# SoftCore_SA_P2_PG6.net
KiCad netlist of a schematic drawn in Altium Designer
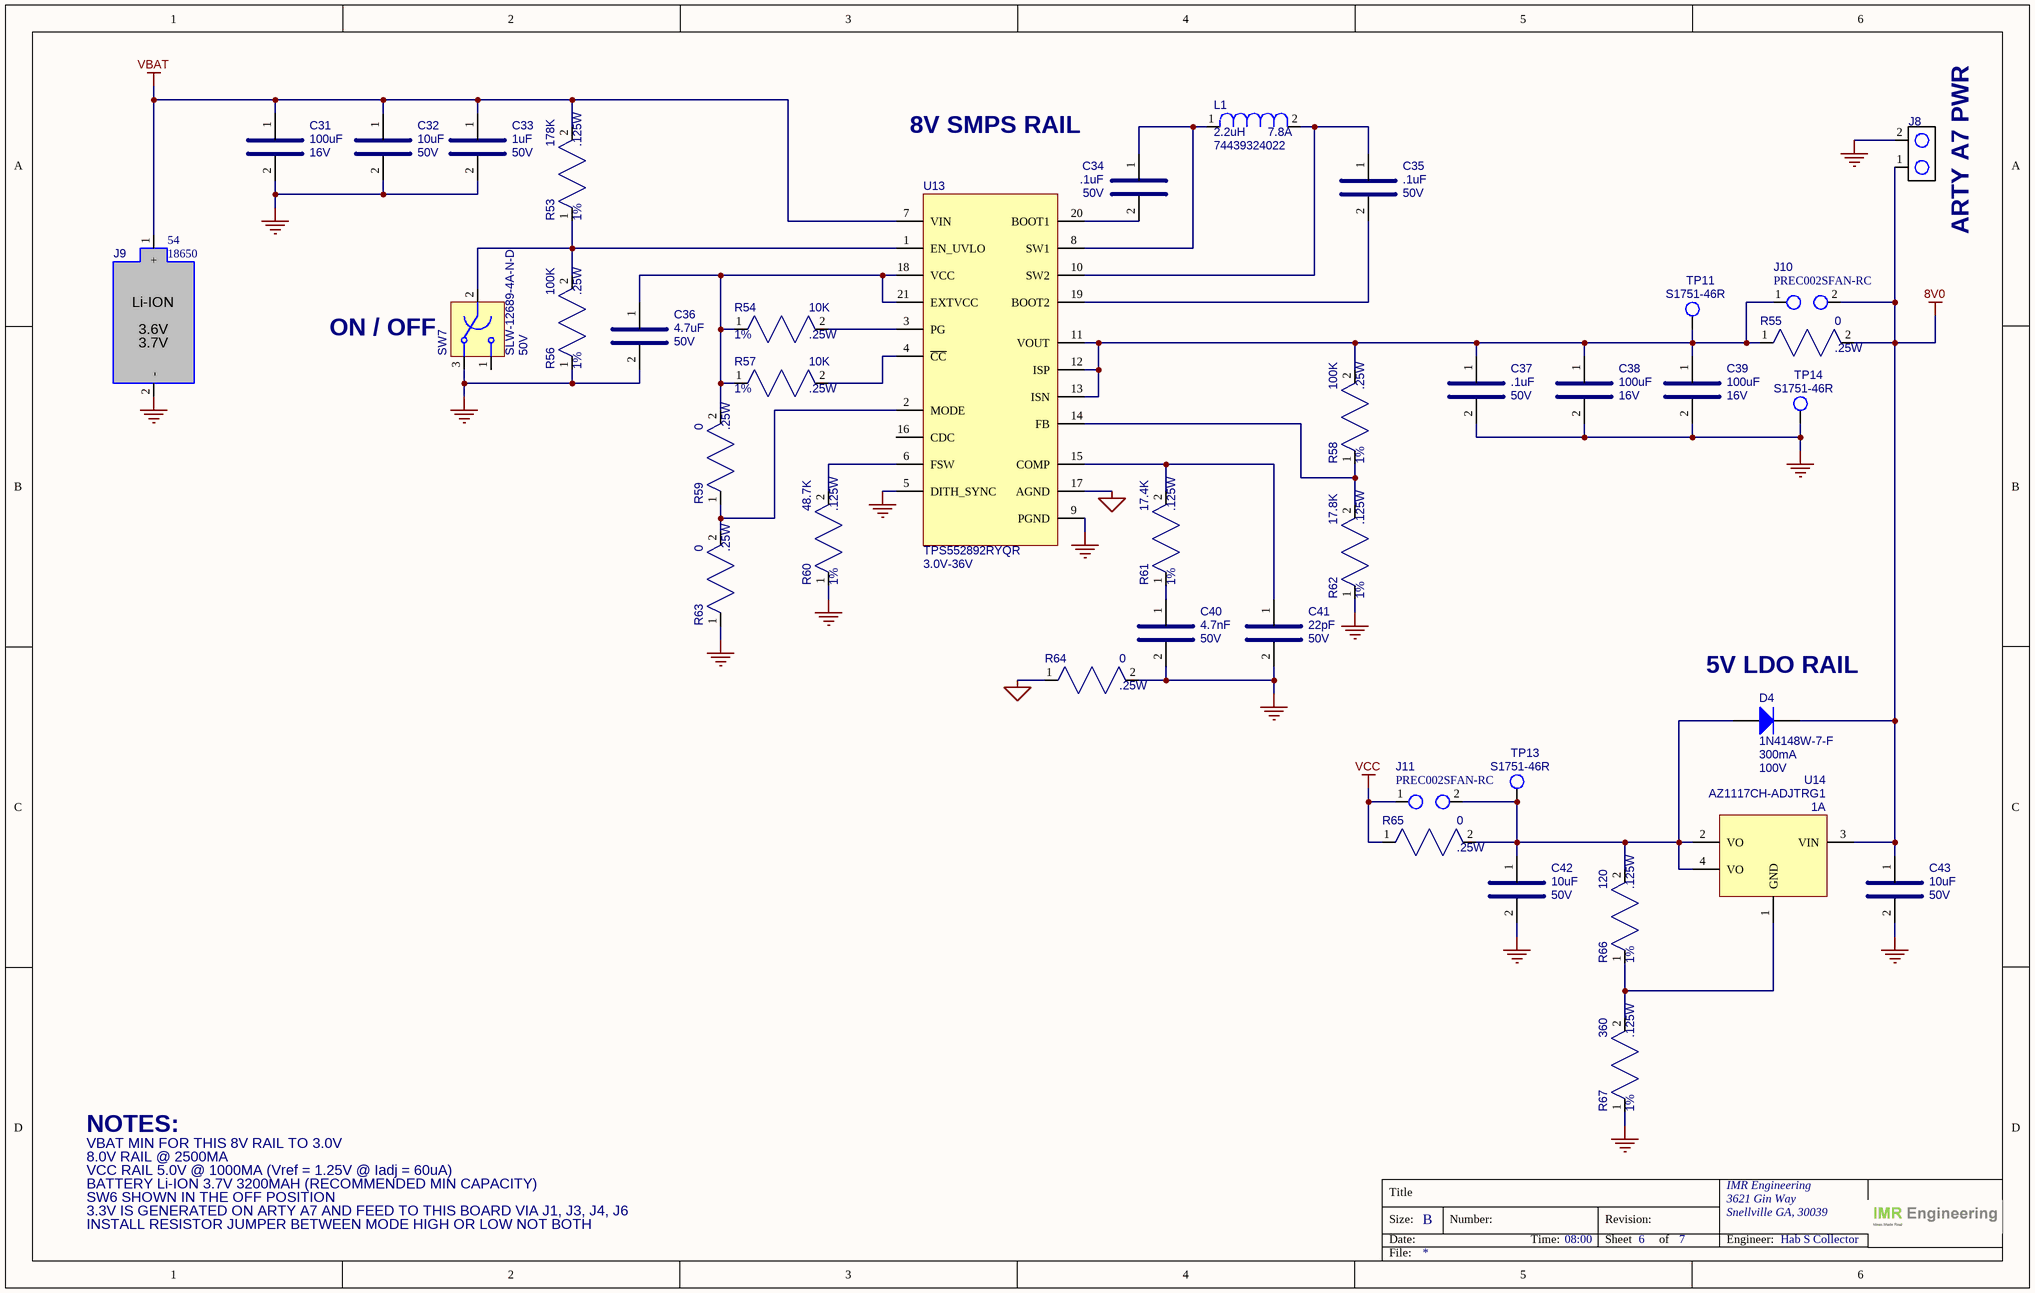
[diagram p0: SoftCore_SA_P2_PG6.SchDoc]

(export (version "E")
  (design (tool "Eeschema 10.0.6"))
  (components
    (comp (ref "C31")
      (value "100uF")
      (footprint "CAP_1210")
      (description "CAP CER 100UF 16V X7S SMD")
      (fields
        (field (name "MFG") "Taiyo Yuden")
        (field (name "VOLTAGE") "16V")
        (field (name "Comment") "EMK325ABJ107MM-P")
      )
      (libsource (lib "IMR_LIB_SCH_R2") (part "CAP_SMD_100UF_16V_SMD"))
    )
    (comp (ref "C32")
      (value "10uF")
      (footprint "CAP_0805")
      (description "CAP CER 10UF 50V X5R 0805")
      (fields
        (field (name "MFG") "Murata Electronics")
        (field (name "VOLTAGE") "50V")
        (field (name "Comment") "GRM21BR61H106KE43L")
      )
      (libsource (lib "IMR_LIB_SCH_R2") (part "CAP_SMD_10UF_50V_0805"))
    )
    (comp (ref "C33")
      (value "1uF")
      (footprint "CAP_0805")
      (description "CAP CER 1UF 50V X7R 0805")
      (fields
        (field (name "MFG") "KYOCERA AVX")
        (field (name "VOLTAGE") "50V")
        (field (name "Comment") "08055C105K4T2A")
      )
      (libsource (lib "IMR_LIB_SCH_R2") (part "CAP_SMD_1UF_50V_0805"))
    )
    (comp (ref "C34")
      (value ".1uF")
      (footprint "CAP_0805")
      (description "CAP CER 0.1UF 50V X7R 0805")
      (fields
        (field (name "MFG") "KYOCERA AVX")
        (field (name "VOLTAGE") "50V")
        (field (name "Comment") "KGM21NR71H104KT")
      )
      (libsource (lib "IMR_LIB_SCH_R2") (part "CAP_SMD_0.1UF_50V_0805"))
    )
    (comp (ref "C35")
      (value ".1uF")
      (footprint "CAP_0805")
      (description "CAP CER 0.1UF 50V X7R 0805")
      (fields
        (field (name "MFG") "KYOCERA AVX")
        (field (name "VOLTAGE") "50V")
        (field (name "Comment") "KGM21NR71H104KT")
      )
      (libsource (lib "IMR_LIB_SCH_R2") (part "CAP_SMD_0.1UF_50V_0805"))
    )
    (comp (ref "C36")
      (value "4.7uF")
      (footprint "CAP_0805")
      (description "CAP CER 4.7UF 50V X5R 0805")
      (fields
        (field (name "MFG") "Murata Electronics")
        (field (name "VOLTAGE") "50V")
        (field (name "Comment") "GRM21BR61H475KE51L")
      )
      (libsource (lib "IMR_LIB_SCH_R2") (part "CAP_SMD_4.7UF_50V_0805"))
    )
    (comp (ref "C37")
      (value ".1uF")
      (footprint "CAP_0805")
      (description "CAP CER 0.1UF 50V X7R 0805")
      (fields
        (field (name "MFG") "KYOCERA AVX")
        (field (name "VOLTAGE") "50V")
        (field (name "Comment") "KGM21NR71H104KT")
      )
      (libsource (lib "IMR_LIB_SCH_R2") (part "CAP_SMD_0.1UF_50V_0805"))
    )
    (comp (ref "C38")
      (value "100uF")
      (footprint "CAP_1210")
      (description "CAP CER 100UF 16V X7S SMD")
      (fields
        (field (name "MFG") "Taiyo Yuden")
        (field (name "VOLTAGE") "16V")
        (field (name "Comment") "EMK325ABJ107MM-P")
      )
      (libsource (lib "IMR_LIB_SCH_R2") (part "CAP_SMD_100UF_16V_SMD"))
    )
    (comp (ref "C39")
      (value "100uF")
      (footprint "CAP_1210")
      (description "CAP CER 100UF 16V X7S SMD")
      (fields
        (field (name "MFG") "Taiyo Yuden")
        (field (name "VOLTAGE") "16V")
        (field (name "Comment") "EMK325ABJ107MM-P")
      )
      (libsource (lib "IMR_LIB_SCH_R2") (part "CAP_SMD_100UF_16V_SMD"))
    )
    (comp (ref "C40")
      (value "4.7nF")
      (footprint "CAP_0805")
      (description "CAP CER 4.7NF 50V X7R 0805")
      (fields
        (field (name "MFG") "KEMET")
        (field (name "VOLTAGE") "50V")
        (field (name "Comment") "C0805C472K5RACAUTO")
      )
      (libsource (lib "IMR_LIB_SCH_R2") (part "CAP_SMD_4.7NF_50V_0805"))
    )
    (comp (ref "C41")
      (value "22pF")
      (footprint "CAP_0805")
      (description "CAP CER 22PF 50V X7R 0805")
      (fields
        (field (name "MFG") "KEMET")
        (field (name "VOLTAGE") "50V")
        (field (name "Comment") "C0805C220K5RACAUTO")
      )
      (libsource (lib "IMR_LIB_SCH_R2") (part "CAP_SMD_22PF_50V_0805"))
    )
    (comp (ref "C42")
      (value "10uF")
      (footprint "CAP_0805")
      (description "CAP CER 10UF 50V X5R 0805")
      (fields
        (field (name "MFG") "Murata Electronics")
        (field (name "VOLTAGE") "50V")
        (field (name "Comment") "GRM21BR61H106KE43L")
      )
      (libsource (lib "IMR_LIB_SCH_R2") (part "CAP_SMD_10UF_50V_0805"))
    )
    (comp (ref "C43")
      (value "10uF")
      (footprint "CAP_0805")
      (description "CAP CER 10UF 50V X5R 0805")
      (fields
        (field (name "MFG") "Murata Electronics")
        (field (name "VOLTAGE") "50V")
        (field (name "Comment") "GRM21BR61H106KE43L")
      )
      (libsource (lib "IMR_LIB_SCH_R2") (part "CAP_SMD_10UF_50V_0805"))
    )
    (comp (ref "D4")
      (value "100V")
      (footprint "SOD123")
      (description "RELAY REED SPDT 250MA 5V")
      (fields
        (field (name "MFG") "Diodes Inc")
        (field (name "MFG_PN") "1N4148W-7-F")
        (field (name "CURRENT") "300mA")
        (field (name "Comment") "1N4148W-7-F")
      )
      (libsource (lib "IMR_LIB_SCH_R2") (part "DIODE_1N4148W-7-F"))
    )
    (comp (ref "J8")
      (value "PREC002SFAN-RC")
      (footprint "HDR_1X2_100MILL")
      (description "CONN HEADER VERT 2POS 2.54MM")
      (fields (field (name "MFG") "Sullins Connector Solutions"))
      (libsource (lib "IMR_LIB_SCH_R2") (part "CONN_HEADER_2P_100MIL_VERT"))
    )
    (comp (ref "J9")
      (value "18650")
      (footprint "CONN_BATTERY_18650")
      (description "CONN HEADER VERT 2POS 2.54MM")
      (fields
        (field (name "MFG") "Keystone Electronics")
        (field (name "MFG_PN") "54")
        (field (name "Comment") "54")
      )
      (libsource (lib "IMR_LIB_SCH_R2") (part "CONN_BATT_18650"))
    )
    (comp (ref "J10")
      (value "PREC002SFAN-RC")
      (footprint "HDR_1X2_100MILL")
      (description "CONN HEADER VERT 2POS 2.54MM")
      (fields (field (name "MFG") "Sullins Connector Solutions"))
      (libsource (lib "IMR_LIB_SCH_R2") (part "CONN_JUMPER_2P_100MIL_VERT"))
    )
    (comp (ref "J11")
      (value "PREC002SFAN-RC")
      (footprint "HDR_1X2_100MILL")
      (description "CONN HEADER VERT 2POS 2.54MM")
      (fields (field (name "MFG") "Sullins Connector Solutions"))
      (libsource (lib "IMR_LIB_SCH_R2") (part "CONN_JUMPER_2P_100MIL_VERT"))
    )
    (comp (ref "L1")
      (value "2.2uH")
      (footprint "WE-XHMI_4030")
      (description "POWER INDUCTOR 4030; 2.2UH; 7.80")
      (fields
        (field (name "MFG") "Würth Elektronik")
        (field (name "TOLERANCE") "20%")
        (field (name "MFG_PN") "74439324022")
        (field (name "CURRENT") "7.8A")
      )
      (libsource (lib "IMR_LIB_SCH_R2") (part "INDUCTOR_74439324022"))
    )
    (comp (ref "R53")
      (value "178K")
      (footprint "RES_0805")
      (description "RES SMD 178K OHM 1% 1/8W 0805")
      (fields
        (field (name "MFG") "Yageo")
        (field (name "POWER") ".125W")
        (field (name "TOLERANCE") "1%")
        (field (name "Comment") "RC0805FR-07178KL")
      )
      (libsource (lib "IMR_LIB_SCH_R2") (part "RES_SMD_178K_0805_1/8W_1%"))
    )
    (comp (ref "R54")
      (value "10K")
      (footprint "RES_0805")
      (description "RES SMD 10K OHM 1% 1/4W 0805")
      (fields
        (field (name "MFG") "Yageo")
        (field (name "POWER") ".25W")
        (field (name "TOLERANCE") "1%")
        (field (name "Comment") "RC0805FR-7W10KL")
      )
      (libsource (lib "IMR_LIB_SCH_R2") (part "RES_SMD_10K_0805_1/4W_1%"))
    )
    (comp (ref "R55")
      (value "0")
      (footprint "RES_0805")
      (description "RES SMD 0 OHM 1% 1/8W 0805")
      (fields (field (name "MFG") "Yageo") (field (name "TOLERANCE") "1%") (field (name "POWER") ".25W"))
      (libsource (lib "IMR_LIB_SCH_R2") (part "RES_SMD_0_0805_1/8W_1%"))
    )
    (comp (ref "R56")
      (value "100K")
      (footprint "RES_0805")
      (description "RES SMD 100K OHM 1% 1/4W 0805")
      (fields
        (field (name "MFG") "Yageo")
        (field (name "POWER") ".25W")
        (field (name "TOLERANCE") "1%")
        (field (name "Comment") "RC0805FR-07100KL")
      )
      (libsource (lib "IMR_LIB_SCH_R2") (part "RES_SMD_100K_0805_1/4W_1%"))
    )
    (comp (ref "R57")
      (value "10K")
      (footprint "RES_0805")
      (description "RES SMD 10K OHM 1% 1/4W 0805")
      (fields
        (field (name "MFG") "Yageo")
        (field (name "POWER") ".25W")
        (field (name "TOLERANCE") "1%")
        (field (name "Comment") "RC0805FR-7W10KL")
      )
      (libsource (lib "IMR_LIB_SCH_R2") (part "RES_SMD_10K_0805_1/4W_1%"))
    )
    (comp (ref "R58")
      (value "100K")
      (footprint "RES_0805")
      (description "RES SMD 100K OHM 1% 1/4W 0805")
      (fields
        (field (name "MFG") "Yageo")
        (field (name "POWER") ".25W")
        (field (name "TOLERANCE") "1%")
        (field (name "Comment") "RC0805FR-07100KL")
      )
      (libsource (lib "IMR_LIB_SCH_R2") (part "RES_SMD_100K_0805_1/4W_1%"))
    )
    (comp (ref "R59")
      (value "0")
      (footprint "RES_0805")
      (description "RES SMD 0 OHM 1% 1/8W 0805")
      (fields (field (name "MFG") "Yageo") (field (name "TOLERANCE") "1%") (field (name "POWER") ".25W"))
      (libsource (lib "IMR_LIB_SCH_R2") (part "RES_SMD_0_0805_1/8W_1%"))
    )
    (comp (ref "R60")
      (value "48.7K")
      (footprint "RES_0805")
      (description "RES SMD 48.7K OHM 1% 1/8W 0805")
      (fields
        (field (name "MFG") "Yageo")
        (field (name "POWER") ".125W")
        (field (name "TOLERANCE") "1%")
        (field (name "Comment") "RC0805FR-0748K7L")
      )
      (libsource (lib "IMR_LIB_SCH_R2") (part "RES_SMD_48.7K_0805_1/8W_1%"))
    )
    (comp (ref "R61")
      (value "17.4K")
      (footprint "RES_0805")
      (description "RES SMD 17.4K OHM 1% 1/8W 0805")
      (fields
        (field (name "MFG") "Yageo")
        (field (name "POWER") ".125W")
        (field (name "TOLERANCE") "1%")
        (field (name "Comment") "RC0805FR-0717K4L")
      )
      (libsource (lib "IMR_LIB_SCH_R2") (part "RES_SMD_17.4K_0805_1/8W_1%"))
    )
    (comp (ref "R62")
      (value "17.8K")
      (footprint "RES_0805")
      (description "RES SMD 17.8K OHM 1% 1/8W 0805")
      (fields
        (field (name "MFG") "Yageo")
        (field (name "POWER") ".125W")
        (field (name "TOLERANCE") "1%")
        (field (name "Comment") "RC0805FR-0717K8L")
      )
      (libsource (lib "IMR_LIB_SCH_R2") (part "RES_SMD_17.8K_0805_1/8W_1%"))
    )
    (comp (ref "R63")
      (value "0")
      (footprint "RES_0805")
      (description "RES SMD 0 OHM 1% 1/8W 0805")
      (fields (field (name "MFG") "Yageo") (field (name "TOLERANCE") "1%") (field (name "POWER") ".25W"))
      (libsource (lib "IMR_LIB_SCH_R2") (part "RES_SMD_0_0805_1/8W_1%"))
    )
    (comp (ref "R64")
      (value "0")
      (footprint "RES_0805")
      (description "RES SMD 0 OHM 1% 1/8W 0805")
      (fields (field (name "MFG") "Yageo") (field (name "TOLERANCE") "1%") (field (name "POWER") ".25W"))
      (libsource (lib "IMR_LIB_SCH_R2") (part "RES_SMD_0_0805_1/8W_1%"))
    )
    (comp (ref "R65")
      (value "0")
      (footprint "RES_0805")
      (description "RES SMD 0 OHM 1% 1/8W 0805")
      (fields (field (name "MFG") "Yageo") (field (name "TOLERANCE") "1%") (field (name "POWER") ".25W"))
      (libsource (lib "IMR_LIB_SCH_R2") (part "RES_SMD_0_0805_1/8W_1%"))
    )
    (comp (ref "R66")
      (value "120")
      (footprint "RES_0805")
      (description "RES SMD 2.49K OHM 1% 1/8W 0805")
      (fields
        (field (name "MFG") "Yageo")
        (field (name "POWER") ".125W")
        (field (name "TOLERANCE") "1%")
        (field (name "Comment") "RC0805FR-132K49L")
      )
      (libsource (lib "IMR_LIB_SCH_R2") (part "RES_SMD_2.49K_0805_1/8W_1%"))
    )
    (comp (ref "R67")
      (value "360")
      (footprint "RES_0805")
      (description "RES SMD 6.81K OHM 1% 1/8W 0805")
      (fields
        (field (name "MFG") "Yageo")
        (field (name "POWER") ".125W")
        (field (name "TOLERANCE") "1%")
        (field (name "Comment") "RC0805FR-076K81L")
      )
      (libsource (lib "IMR_LIB_SCH_R2") (part "RES_SMD_6.81K_0805_1/8W_1%"))
    )
    (comp (ref "SW7")
      (value "50V")
      (footprint "SLW126894AND")
      (description "SWITCH SLIDE SPDT 300MA 50V")
      (fields
        (field (name "MFG") "Same Sky")
        (field (name "MFG_PN") "SLW-12689-4A-N-D")
        (field (name "Comment") "SLW-12689-4A-N-D")
      )
      (libsource (lib "IMR_LIB_SCH_R2") (part "SWITCH_SLW-12689-4A-N-D"))
    )
    (comp (ref "TP11")
      (value "S1751-46R")
      (footprint "HARWIN_S1751")
      (description "PCB TEST POINT CONNECT")
      (fields (field (name "MFG") "Harwin Inc") (field (name "MFG_PN") "S1751-46R"))
      (libsource (lib "IMR_LIB_SCH_R2") (part "CONN_TEST_POINT_S1751-46R"))
    )
    (comp (ref "TP13")
      (value "S1751-46R")
      (footprint "HARWIN_S1751")
      (description "PCB TEST POINT CONNECT")
      (fields (field (name "MFG") "Harwin Inc") (field (name "MFG_PN") "S1751-46R"))
      (libsource (lib "IMR_LIB_SCH_R2") (part "CONN_TEST_POINT_S1751-46R"))
    )
    (comp (ref "TP14")
      (value "S1751-46R")
      (footprint "HARWIN_S1751")
      (description "PCB TEST POINT CONNECT")
      (fields (field (name "MFG") "Harwin Inc") (field (name "MFG_PN") "S1751-46R"))
      (libsource (lib "IMR_LIB_SCH_R2") (part "CONN_TEST_POINT_S1751-46R"))
    )
    (comp (ref "U13")
      (value "3.0V-36V")
      (footprint "CONV_TPS552892RYQR")
      (description "IC REG BUCK ADJ 1A 16HTSSOP")
      (fields
        (field (name "MFG") "Texas Instruments")
        (field (name "MFG_PN") "TPS552892RYQR")
        (field (name "Comment") "TPS552892RYQR")
      )
      (libsource (lib "IMR_LIB_SCH_R2") (part "IC_SMPS_TPS552892RYQR"))
    )
    (comp (ref "U14")
      (value "AZ1117CH-ADJTRG1")
      (footprint "SOT223")
      (description "IC REG BUCK ADJ 2A SOT23")
      (fields
        (field (name "MFG") "Diodes Incorporated")
        (field (name "CURRENT") "1A")
        (field (name "MFG_PN") "AZ1117CH-ADJTRG1")
      )
      (libsource (lib "IMR_LIB_SCH_R2") (part "IC_REG_AZ1117CH-ADJTRG1"))
    )
  )
  (nets
    (net (code "1") (name "8V0") (class "Default")
      (node (ref "C43") (pin "1") (pinfunction "1_1") (pintype "passive"))
      (node (ref "D4") (pin "2") (pinfunction "K_2") (pintype "passive"))
      (node (ref "J10") (pin "2") (pintype "passive"))
      (node (ref "J8") (pin "1") (pintype "passive"))
      (node (ref "R55") (pin "2") (pinfunction "2_2") (pintype "passive"))
      (node (ref "U14") (pin "3") (pinfunction "VIN_3") (pintype "passive"))
    )
    (net (code "2") (name "AGND") (class "Default")
      (node (ref "R64") (pin "1") (pinfunction "1_1") (pintype "passive"))
      (node (ref "U13") (pin "17") (pinfunction "AGND_17") (pintype "passive"))
    )
    (net (code "3") (name "GND") (class "Default")
      (node (ref "C31") (pin "2") (pinfunction "2_2") (pintype "passive"))
      (node (ref "C32") (pin "2") (pinfunction "2_2") (pintype "passive"))
      (node (ref "C33") (pin "2") (pinfunction "2_2") (pintype "passive"))
      (node (ref "C36") (pin "2") (pinfunction "2_2") (pintype "passive"))
      (node (ref "C37") (pin "2") (pinfunction "2_2") (pintype "passive"))
      (node (ref "C38") (pin "2") (pinfunction "2_2") (pintype "passive"))
      (node (ref "C39") (pin "2") (pinfunction "2_2") (pintype "passive"))
      (node (ref "C40") (pin "2") (pinfunction "2_2") (pintype "passive"))
      (node (ref "C41") (pin "2") (pinfunction "2_2") (pintype "passive"))
      (node (ref "C42") (pin "2") (pinfunction "2_2") (pintype "passive"))
      (node (ref "C43") (pin "2") (pinfunction "2_2") (pintype "passive"))
      (node (ref "J8") (pin "2") (pintype "passive"))
      (node (ref "J9") (pin "2") (pinfunction "-_2") (pintype "passive"))
      (node (ref "R56") (pin "1") (pinfunction "1_1") (pintype "passive"))
      (node (ref "R60") (pin "1") (pinfunction "1_1") (pintype "passive"))
      (node (ref "R62") (pin "1") (pinfunction "1_1") (pintype "passive"))
      (node (ref "R63") (pin "1") (pinfunction "1_1") (pintype "passive"))
      (node (ref "R64") (pin "2") (pinfunction "2_2") (pintype "passive"))
      (node (ref "R67") (pin "1") (pinfunction "1_1") (pintype "passive"))
      (node (ref "SW7") (pin "3") (pintype "passive"))
      (node (ref "TP14") (pin "1") (pintype "passive"))
      (node (ref "U13") (pin "5") (pinfunction "DITH_SYNC_5") (pintype "passive"))
      (node (ref "U13") (pin "9") (pinfunction "PGND_9") (pintype "passive"))
    )
    (net (code "4") (name "Net-(C40-Pad1)") (class "Default")
      (node (ref "C40") (pin "1") (pinfunction "1_1") (pintype "passive"))
      (node (ref "R61") (pin "1") (pinfunction "1_1") (pintype "passive"))
    )
    (net (code "5") (name "Net-(D4-A)") (class "Default")
      (node (ref "C42") (pin "1") (pinfunction "1_1") (pintype "passive"))
      (node (ref "D4") (pin "1") (pinfunction "A_1") (pintype "passive"))
      (node (ref "J11") (pin "2") (pintype "passive"))
      (node (ref "R65") (pin "2") (pinfunction "2_2") (pintype "passive"))
      (node (ref "R66") (pin "2") (pinfunction "2_2") (pintype "passive"))
      (node (ref "TP13") (pin "1") (pintype "passive"))
      (node (ref "U14") (pin "2") (pinfunction "VO_2") (pintype "passive"))
      (node (ref "U14") (pin "4") (pinfunction "VO_4") (pintype "passive"))
    )
    (net (code "6") (name "Net-(U13-BOOT1)") (class "Default")
      (node (ref "C34") (pin "2") (pinfunction "2_2") (pintype "passive"))
      (node (ref "U13") (pin "20") (pinfunction "BOOT1_20") (pintype "passive"))
    )
    (net (code "7") (name "Net-(U13-BOOT2)") (class "Default")
      (node (ref "C35") (pin "2") (pinfunction "2_2") (pintype "passive"))
      (node (ref "U13") (pin "19") (pinfunction "BOOT2_19") (pintype "passive"))
    )
    (net (code "8") (name "Net-(U13-COMP)") (class "Default")
      (node (ref "C41") (pin "1") (pinfunction "1_1") (pintype "passive"))
      (node (ref "R61") (pin "2") (pinfunction "2_2") (pintype "passive"))
      (node (ref "U13") (pin "15") (pinfunction "COMP_15") (pintype "passive"))
    )
    (net (code "9") (name "Net-(U13-EN_UVLO)") (class "Default")
      (node (ref "R53") (pin "1") (pinfunction "1_1") (pintype "passive"))
      (node (ref "R56") (pin "2") (pinfunction "2_2") (pintype "passive"))
      (node (ref "SW7") (pin "2") (pintype "passive"))
      (node (ref "U13") (pin "1") (pinfunction "EN_UVLO_1") (pintype "passive"))
    )
    (net (code "10") (name "Net-(U13-EXTVCC)") (class "Default")
      (node (ref "C36") (pin "1") (pinfunction "1_1") (pintype "passive"))
      (node (ref "R54") (pin "1") (pinfunction "1_1") (pintype "passive"))
      (node (ref "R57") (pin "1") (pinfunction "1_1") (pintype "passive"))
      (node (ref "R59") (pin "2") (pinfunction "2_2") (pintype "passive"))
      (node (ref "U13") (pin "18") (pinfunction "VCC_18") (pintype "passive"))
      (node (ref "U13") (pin "21") (pinfunction "EXTVCC_21") (pintype "passive"))
    )
    (net (code "11") (name "Net-(U13-FB)") (class "Default")
      (node (ref "R58") (pin "1") (pinfunction "1_1") (pintype "passive"))
      (node (ref "R62") (pin "2") (pinfunction "2_2") (pintype "passive"))
      (node (ref "U13") (pin "14") (pinfunction "FB_14") (pintype "passive"))
    )
    (net (code "12") (name "Net-(U13-FSW)") (class "Default")
      (node (ref "R60") (pin "2") (pinfunction "2_2") (pintype "passive"))
      (node (ref "U13") (pin "6") (pinfunction "FSW_6") (pintype "passive"))
    )
    (net (code "13") (name "Net-(U13-ISN)") (class "Default")
      (node (ref "C37") (pin "1") (pinfunction "1_1") (pintype "passive"))
      (node (ref "C38") (pin "1") (pinfunction "1_1") (pintype "passive"))
      (node (ref "C39") (pin "1") (pinfunction "1_1") (pintype "passive"))
      (node (ref "J10") (pin "1") (pintype "passive"))
      (node (ref "R55") (pin "1") (pinfunction "1_1") (pintype "passive"))
      (node (ref "R58") (pin "2") (pinfunction "2_2") (pintype "passive"))
      (node (ref "TP11") (pin "1") (pintype "passive"))
      (node (ref "U13") (pin "11") (pinfunction "VOUT_11") (pintype "passive"))
      (node (ref "U13") (pin "12") (pinfunction "ISP_12") (pintype "passive"))
      (node (ref "U13") (pin "13") (pinfunction "ISN_13") (pintype "passive"))
    )
    (net (code "14") (name "Net-(U13-MODE)") (class "Default")
      (node (ref "R59") (pin "1") (pinfunction "1_1") (pintype "passive"))
      (node (ref "R63") (pin "2") (pinfunction "2_2") (pintype "passive"))
      (node (ref "U13") (pin "2") (pinfunction "MODE_2") (pintype "passive"))
    )
    (net (code "15") (name "Net-(U13-PG)") (class "Default")
      (node (ref "R54") (pin "2") (pinfunction "2_2") (pintype "passive"))
      (node (ref "U13") (pin "3") (pinfunction "PG_3") (pintype "passive"))
    )
    (net (code "16") (name "Net-(U13-SW1)") (class "Default")
      (node (ref "C34") (pin "1") (pinfunction "1_1") (pintype "passive"))
      (node (ref "L1") (pin "1") (pinfunction "1_1") (pintype "passive"))
      (node (ref "U13") (pin "8") (pinfunction "SW1_8") (pintype "passive"))
    )
    (net (code "17") (name "Net-(U13-SW2)") (class "Default")
      (node (ref "C35") (pin "1") (pinfunction "1_1") (pintype "passive"))
      (node (ref "L1") (pin "2") (pinfunction "2_2") (pintype "passive"))
      (node (ref "U13") (pin "10") (pinfunction "SW2_10") (pintype "passive"))
    )
    (net (code "18") (name "Net-(U13-~{CC})") (class "Default")
      (node (ref "R57") (pin "2") (pinfunction "2_2") (pintype "passive"))
      (node (ref "U13") (pin "4") (pinfunction "~{CC}_4") (pintype "passive"))
    )
    (net (code "19") (name "Net-(U14-GND)") (class "Default")
      (node (ref "R66") (pin "1") (pinfunction "1_1") (pintype "passive"))
      (node (ref "R67") (pin "2") (pinfunction "2_2") (pintype "passive"))
      (node (ref "U14") (pin "1") (pinfunction "GND_1") (pintype "passive"))
    )
    (net (code "20") (name "VBAT") (class "Default")
      (node (ref "C31") (pin "1") (pinfunction "1_1") (pintype "passive"))
      (node (ref "C32") (pin "1") (pinfunction "1_1") (pintype "passive"))
      (node (ref "C33") (pin "1") (pinfunction "1_1") (pintype "passive"))
      (node (ref "J9") (pin "1") (pinfunction "+_1") (pintype "passive"))
      (node (ref "R53") (pin "2") (pinfunction "2_2") (pintype "passive"))
      (node (ref "U13") (pin "7") (pinfunction "VIN_7") (pintype "passive"))
    )
    (net (code "21") (name "VCC") (class "Default")
      (node (ref "J11") (pin "1") (pintype "passive"))
      (node (ref "R65") (pin "1") (pinfunction "1_1") (pintype "passive"))
    )
    (net (code "22") (name "unconnected-(SW7-Pad1)") (class "Default")
      (node (ref "SW7") (pin "1") (pintype "passive"))
    )
    (net (code "23") (name "unconnected-(U13-CDC-Pad16)") (class "Default")
      (node (ref "U13") (pin "16") (pinfunction "CDC_16") (pintype "passive"))
    )
  )
)
